# IoT_Greenhouse_V1_0_A_-_Pwr_Input.net
KiCad netlist of a schematic drawn in Altium Designer
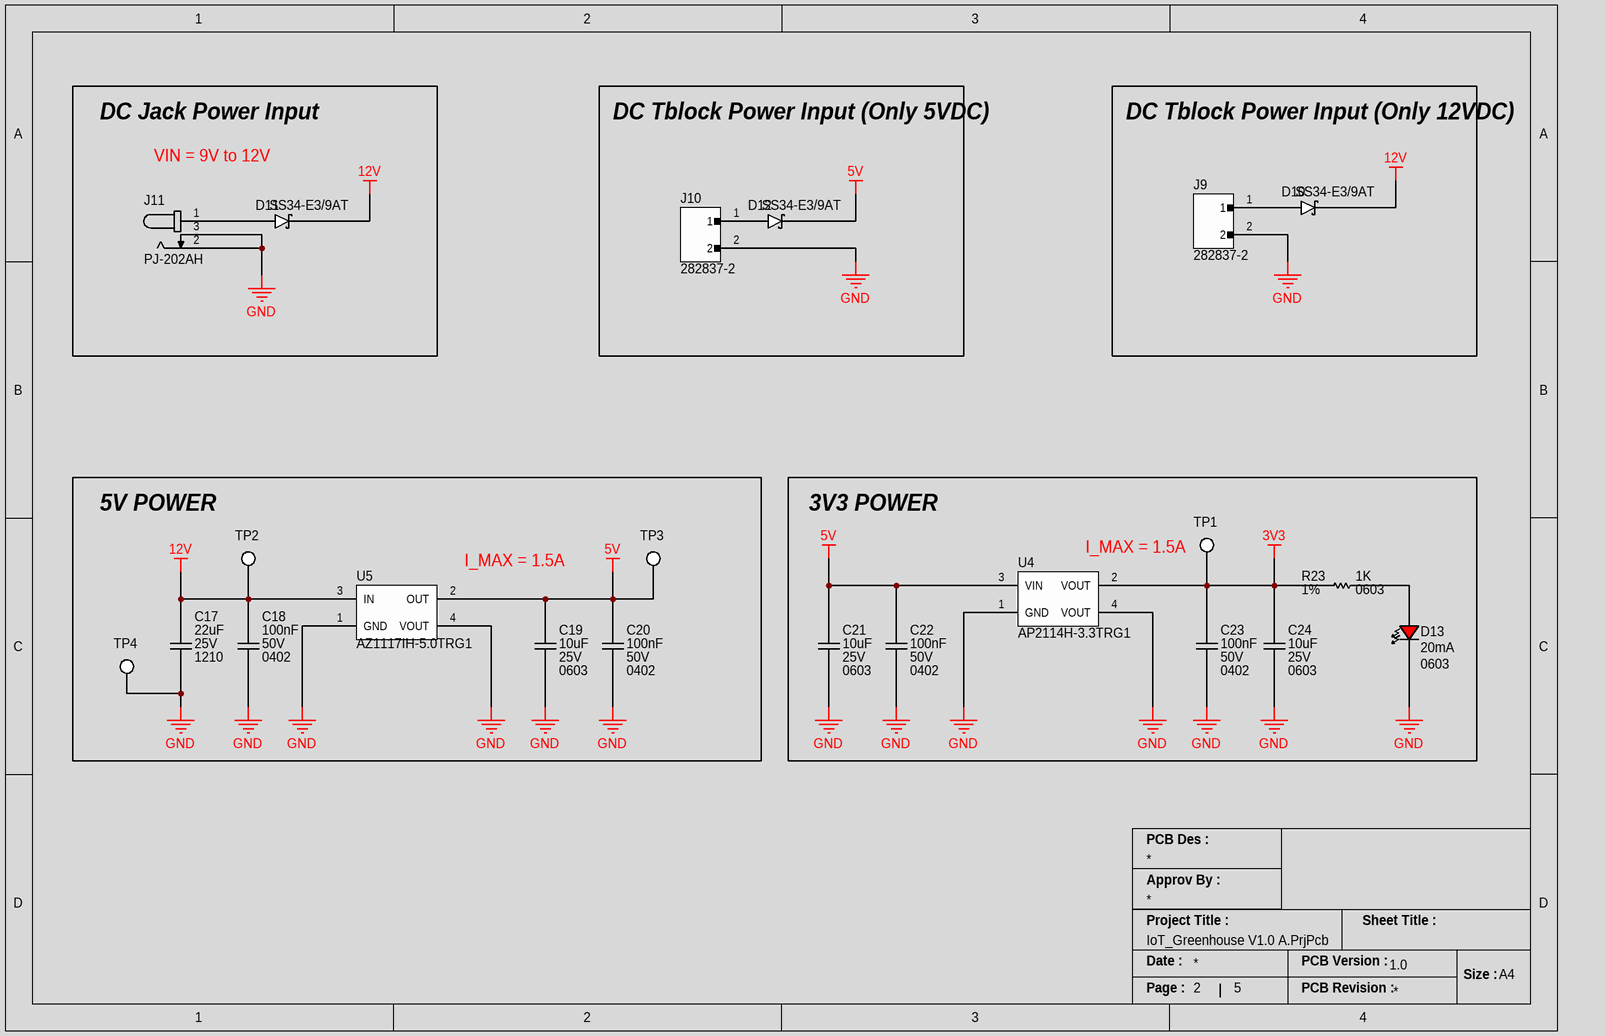
[diagram p0: IoT_Greenhouse V1.0 A - Pwr Input.SchDoc]

(export (version "E")
  (design (tool "Eeschema 10.0.6"))
  (components
    (comp (ref "C17")
      (value "GRM32ER71E226KE15L")
      (footprint "CAP_1210_CAPC3225X270N")
      (description "Multilayer Ceramic Capacitor, 22 uF, 25 V, ± 10%, X7R, 1210 [3225 Metric]")
      (fields
        (field (name "MANUFACTURER") "Murata")
        (field (name "TOLERANCE") "10%")
        (field (name "VOLTAGE RATING") "25V")
        (field (name "CAPACITANCE") "22uF")
        (field (name "CASE/PACKAGE") "1210")
      )
      (libsource (lib "Electronic Devices_LIB") (part "CAP_22UF_25V_X7R_1210"))
    )
    (comp (ref "C18")
      (value "GRM155R71H104KE14D")
      (footprint "CAP_0402_CAPC1005X05N")
      (description "Multilayer Ceramic Capacitor, 0.1 uF, 16 V, ± 10%, X7R, 0402 [1005 Metric]")
      (fields
        (field (name "MANUFACTURER") "Murata")
        (field (name "TOLERANCE") "10%")
        (field (name "VOLTAGE RATING") "50V")
        (field (name "CAPACITANCE") "100nF")
        (field (name "CASE/PACKAGE") "0402")
      )
      (libsource (lib "Electronic Devices_LIB") (part "CAP_100NF_50V_X7R_0402"))
    )
    (comp (ref "C19")
      (value "GRM188R61E106MA73D")
      (footprint "CAP_0603_CAPC1608X08N")
      (description "Multilayer Ceramic Capacitor, 10 uF, 25 V, ± 20%, X5R, 0603 [1608 Metric]")
      (fields
        (field (name "MANUFACTURER") "Murata")
        (field (name "TOLERANCE") "20%")
        (field (name "CASE/PACKAGE") "0603")
        (field (name "CAPACITANCE") "10uF")
        (field (name "VOLTAGE RATING") "25V")
      )
      (libsource (lib "Electronic Devices_LIB") (part "CAP_10UF_25V_X5R_0603"))
    )
    (comp (ref "C20")
      (value "GRM155R71H104KE14D")
      (footprint "CAP_0402_CAPC1005X05N")
      (description "Multilayer Ceramic Capacitor, 0.1 uF, 16 V, ± 10%, X7R, 0402 [1005 Metric]")
      (fields
        (field (name "MANUFACTURER") "Murata")
        (field (name "TOLERANCE") "10%")
        (field (name "VOLTAGE RATING") "50V")
        (field (name "CAPACITANCE") "100nF")
        (field (name "CASE/PACKAGE") "0402")
      )
      (libsource (lib "Electronic Devices_LIB") (part "CAP_100NF_50V_X7R_0402"))
    )
    (comp (ref "C21")
      (value "GRM188R61E106MA73D")
      (footprint "CAP_0603_CAPC1608X08N")
      (description "Multilayer Ceramic Capacitor, 10 uF, 25 V, ± 20%, X5R, 0603 [1608 Metric]")
      (fields
        (field (name "MANUFACTURER") "Murata")
        (field (name "TOLERANCE") "20%")
        (field (name "CASE/PACKAGE") "0603")
        (field (name "CAPACITANCE") "10uF")
        (field (name "VOLTAGE RATING") "25V")
      )
      (libsource (lib "Electronic Devices_LIB") (part "CAP_10UF_25V_X5R_0603"))
    )
    (comp (ref "C22")
      (value "GRM155R71H104KE14D")
      (footprint "CAP_0402_CAPC1005X05N")
      (description "Multilayer Ceramic Capacitor, 0.1 uF, 16 V, ± 10%, X7R, 0402 [1005 Metric]")
      (fields
        (field (name "MANUFACTURER") "Murata")
        (field (name "TOLERANCE") "10%")
        (field (name "VOLTAGE RATING") "50V")
        (field (name "CAPACITANCE") "100nF")
        (field (name "CASE/PACKAGE") "0402")
      )
      (libsource (lib "Electronic Devices_LIB") (part "CAP_100NF_50V_X7R_0402"))
    )
    (comp (ref "C23")
      (value "GRM155R71H104KE14D")
      (footprint "CAP_0402_CAPC1005X05N")
      (description "Multilayer Ceramic Capacitor, 0.1 uF, 16 V, ± 10%, X7R, 0402 [1005 Metric]")
      (fields
        (field (name "MANUFACTURER") "Murata")
        (field (name "TOLERANCE") "10%")
        (field (name "VOLTAGE RATING") "50V")
        (field (name "CAPACITANCE") "100nF")
        (field (name "CASE/PACKAGE") "0402")
      )
      (libsource (lib "Electronic Devices_LIB") (part "CAP_100NF_50V_X7R_0402"))
    )
    (comp (ref "C24")
      (value "GRM188R61E106MA73D")
      (footprint "CAP_0603_CAPC1608X08N")
      (description "Multilayer Ceramic Capacitor, 10 uF, 25 V, ± 20%, X5R, 0603 [1608 Metric]")
      (fields
        (field (name "MANUFACTURER") "Murata")
        (field (name "TOLERANCE") "20%")
        (field (name "CASE/PACKAGE") "0603")
        (field (name "CAPACITANCE") "10uF")
        (field (name "VOLTAGE RATING") "25V")
      )
      (libsource (lib "Electronic Devices_LIB") (part "CAP_10UF_25V_X5R_0603"))
    )
    (comp (ref "D10")
      (value "SS34-E3/9AT")
      (footprint "DIO_Vishay_SMC_MFG")
      (description "Rectifier Diode, schottky, 40V V(Rrm), do-214Ab / Smc")
      (fields (field (name "MANUFACTURER") "Vishay Semiconductors"))
      (libsource (lib "Electronic Devices_LIB") (part "DIO_SCTKY_40V_3A"))
    )
    (comp (ref "D11")
      (value "SS34-E3/9AT")
      (footprint "DIO_Vishay_SMC_MFG")
      (description "Rectifier Diode, schottky, 40V V(Rrm), do-214Ab / Smc")
      (fields (field (name "MANUFACTURER") "Vishay Semiconductors"))
      (libsource (lib "Electronic Devices_LIB") (part "DIO_SCTKY_40V_3A"))
    )
    (comp (ref "D12")
      (value "SS34-E3/9AT")
      (footprint "DIO_Vishay_SMC_MFG")
      (description "Rectifier Diode, schottky, 40V V(Rrm), do-214Ab / Smc")
      (fields (field (name "MANUFACTURER") "Vishay Semiconductors"))
      (libsource (lib "Electronic Devices_LIB") (part "DIO_SCTKY_40V_3A"))
    )
    (comp (ref "D13")
      (value "LTST-C190KRKT")
      (footprint "LED_0603-RED-0.75mm")
      (description "LED,  LTST-C190KRKT")
      (fields
        (field (name "MANUFACTURER") "Vishay Lite-On")
        (field (name "TEST CURRENT") "20mA")
        (field (name "CASE/PACKAGE") "0603")
      )
      (libsource (lib "Electronic Devices_LIB") (part "LED_DIO_RED_20mA_0603"))
    )
    (comp (ref "J9")
      (value "282837-2")
      (footprint "CONN_TBLOCK_2P_{backslash}2828372")
      (description "Connector, Terminal Block; Wire Receptacle; 2 Pos.; 16-30 AWG; 0.2 in. CL; Side;")
      (fields (field (name "MANUFACTURER") "TE Connectivity") (field (name "VOLTAGE") "300V"))
      (libsource (lib "Electronic Devices_LIB") (part "CONN_TBLOCK_2P_5.08mm_282837-2"))
    )
    (comp (ref "J10")
      (value "282837-2")
      (footprint "CONN_TBLOCK_2P_{backslash}2828372")
      (description "Connector, Terminal Block; Wire Receptacle; 2 Pos.; 16-30 AWG; 0.2 in. CL; Side;")
      (fields (field (name "MANUFACTURER") "TE Connectivity") (field (name "VOLTAGE") "300V"))
      (libsource (lib "Electronic Devices_LIB") (part "CONN_TBLOCK_2P_5.08mm_282837-2"))
    )
    (comp (ref "J11")
      (value "PJ-202AH")
      (footprint "CONN_CUI_PJ-202AH")
      (description "2.0 x 6.5 mm, 5.0 A, Horizontal, Through Hole, Kinked Pins, Dc Power Jack Connector")
      (fields (field (name "MANUFACTURER") "CUI Devices"))
      (libsource (lib "Electronic Devices_LIB") (part "CONN_DC_JACK_2X6.5mm_PJ-202AH"))
    )
    (comp (ref "R23")
      (value "AC0603FR-101KL")
      (footprint "RES_0603_RESC1608X04N")
      (description "Chip Resistor Automotive Grade Thick Film 0603 1kOhm 1% Paper T/R")
      (fields
        (field (name "MANUFACTURER") "Yageo")
        (field (name "RESISTANCE") "1K")
        (field (name "TOLERANCE") "1%")
        (field (name "CASE/PACKAGE") "0603")
      )
      (libsource (lib "Electronic Devices_LIB") (part "RES_1K_1%_100mW_0603"))
    )
    (comp (ref "TP1")
      (value "NO COMPONENT")
      (footprint "TP_PAD_1.6MM_SMD_ROUND")
      (description "Test Point, SMD pad, round, 1.5mm, 1.6mm, 3mm diameter")
      (libsource (lib "Electronic Devices_LIB") (part "TP_PAD_SMD_Round"))
    )
    (comp (ref "TP2")
      (value "NO COMPONENT")
      (footprint "TP_PAD_1.6MM_SMD_ROUND")
      (description "Test Point, SMD pad, round, 1.5mm, 1.6mm, 3mm diameter")
      (libsource (lib "Electronic Devices_LIB") (part "TP_PAD_SMD_Round"))
    )
    (comp (ref "TP3")
      (value "NO COMPONENT")
      (footprint "TP_PAD_1.6MM_SMD_ROUND")
      (description "Test Point, SMD pad, round, 1.5mm, 1.6mm, 3mm diameter")
      (libsource (lib "Electronic Devices_LIB") (part "TP_PAD_SMD_Round"))
    )
    (comp (ref "TP4")
      (value "NO COMPONENT")
      (footprint "TP_PAD_1.6MM_SMD_ROUND")
      (description "Test Point, SMD pad, round, 1.5mm, 1.6mm, 3mm diameter")
      (libsource (lib "Electronic Devices_LIB") (part "TP_PAD_SMD_Round"))
    )
    (comp (ref "U4")
      (value "AP2114H-3.3TRG1")
      (footprint "IC_REG_SOT230P700X180-4N")
      (description "IC REG LDO 3.3V 1A SOT223")
      (fields (field (name "MANUFACTURER") "Diodes"))
      (libsource (lib "Electronic Devices_LIB") (part "IC_REG_LDO_3.3V_1A_AP2114H-3.3TRG1"))
    )
    (comp (ref "U5")
      (value "AZ1117IH-5.0TRG1")
      (footprint "IC_REG_SOT230P700X180-4N")
      (description "LDO Regulator Pos 5V 1A 3-Pin SOT-223 T/R")
      (fields (field (name "MANUFACTURER") "Diodes"))
      (libsource (lib "Electronic Devices_LIB") (part "IC_REG_LDO_5V_1A_AZ1117IH-5.0TRG1"))
    )
  )
  (nets
    (net (code "1") (name "3V3") (class "Default")
      (node (ref "C23") (pin "2") (pinfunction "2_2") (pintype "passive"))
      (node (ref "C24") (pin "2") (pinfunction "2_2") (pintype "passive"))
      (node (ref "R23") (pin "1") (pinfunction "1_1") (pintype "passive"))
      (node (ref "TP1") (pin "1") (pinfunction "1_1") (pintype "passive"))
      (node (ref "U4") (pin "2") (pinfunction "VOUT_2") (pintype "passive"))
    )
    (net (code "2") (name "5V") (class "Default")
      (node (ref "C19") (pin "2") (pinfunction "2_2") (pintype "passive"))
      (node (ref "C20") (pin "2") (pinfunction "2_2") (pintype "passive"))
      (node (ref "C21") (pin "2") (pinfunction "2_2") (pintype "passive"))
      (node (ref "C22") (pin "2") (pinfunction "2_2") (pintype "passive"))
      (node (ref "D12") (pin "1") (pinfunction "K_1") (pintype "passive"))
      (node (ref "TP3") (pin "1") (pinfunction "1_1") (pintype "passive"))
      (node (ref "U4") (pin "3") (pinfunction "VIN_3") (pintype "passive"))
      (node (ref "U5") (pin "2") (pinfunction "OUT_2") (pintype "passive"))
    )
    (net (code "3") (name "12V") (class "Default")
      (node (ref "C17") (pin "2") (pinfunction "2_2") (pintype "passive"))
      (node (ref "C18") (pin "2") (pinfunction "2_2") (pintype "passive"))
      (node (ref "D10") (pin "1") (pinfunction "K_1") (pintype "passive"))
      (node (ref "D11") (pin "1") (pinfunction "K_1") (pintype "passive"))
      (node (ref "TP2") (pin "1") (pinfunction "1_1") (pintype "passive"))
      (node (ref "U5") (pin "3") (pinfunction "IN_3") (pintype "passive"))
    )
    (net (code "4") (name "GND") (class "Default")
      (node (ref "C17") (pin "1") (pinfunction "1_1") (pintype "passive"))
      (node (ref "C18") (pin "1") (pinfunction "1_1") (pintype "passive"))
      (node (ref "C19") (pin "1") (pinfunction "1_1") (pintype "passive"))
      (node (ref "C20") (pin "1") (pinfunction "1_1") (pintype "passive"))
      (node (ref "C21") (pin "1") (pinfunction "1_1") (pintype "passive"))
      (node (ref "C22") (pin "1") (pinfunction "1_1") (pintype "passive"))
      (node (ref "C23") (pin "1") (pinfunction "1_1") (pintype "passive"))
      (node (ref "C24") (pin "1") (pinfunction "1_1") (pintype "passive"))
      (node (ref "D13") (pin "1") (pinfunction "C_1") (pintype "passive"))
      (node (ref "J10") (pin "2") (pinfunction "2_2") (pintype "passive"))
      (node (ref "J11") (pin "2") (pinfunction "2_2") (pintype "passive"))
      (node (ref "J11") (pin "3") (pinfunction "3_3") (pintype "passive"))
      (node (ref "J9") (pin "2") (pinfunction "2_2") (pintype "passive"))
      (node (ref "TP4") (pin "1") (pinfunction "1_1") (pintype "passive"))
      (node (ref "U4") (pin "1") (pinfunction "GND_1") (pintype "passive"))
      (node (ref "U4") (pin "4") (pinfunction "VOUT_4") (pintype "passive"))
      (node (ref "U5") (pin "1") (pinfunction "GND_1") (pintype "passive"))
      (node (ref "U5") (pin "4") (pinfunction "VOUT_4") (pintype "passive"))
    )
    (net (code "5") (name "Net-(D10-A)") (class "Default")
      (node (ref "D10") (pin "2") (pinfunction "A_2") (pintype "passive"))
      (node (ref "J9") (pin "1") (pinfunction "1_1") (pintype "passive"))
    )
    (net (code "6") (name "Net-(D11-A)") (class "Default")
      (node (ref "D11") (pin "2") (pinfunction "A_2") (pintype "passive"))
      (node (ref "J11") (pin "1") (pinfunction "1_1") (pintype "passive"))
    )
    (net (code "7") (name "Net-(D12-A)") (class "Default")
      (node (ref "D12") (pin "2") (pinfunction "A_2") (pintype "passive"))
      (node (ref "J10") (pin "1") (pinfunction "1_1") (pintype "passive"))
    )
    (net (code "8") (name "Net-(D13-A)") (class "Default")
      (node (ref "D13") (pin "2") (pinfunction "A_2") (pintype "passive"))
      (node (ref "R23") (pin "2") (pinfunction "2_2") (pintype "passive"))
    )
  )
)
